# se_to_diff_v0001.net
KiCad netlist of a schematic drawn in EAGLE
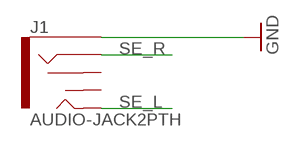
[diagram p0: schematic, sheet 1]
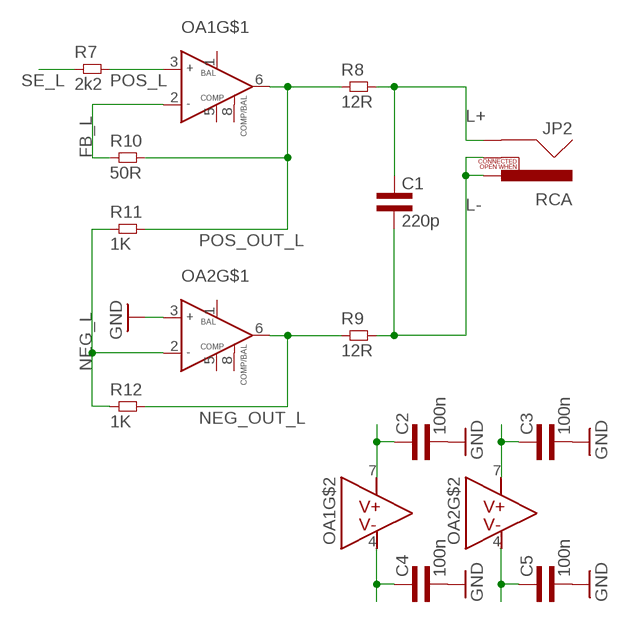
[diagram p1: schematic, sheet 2]
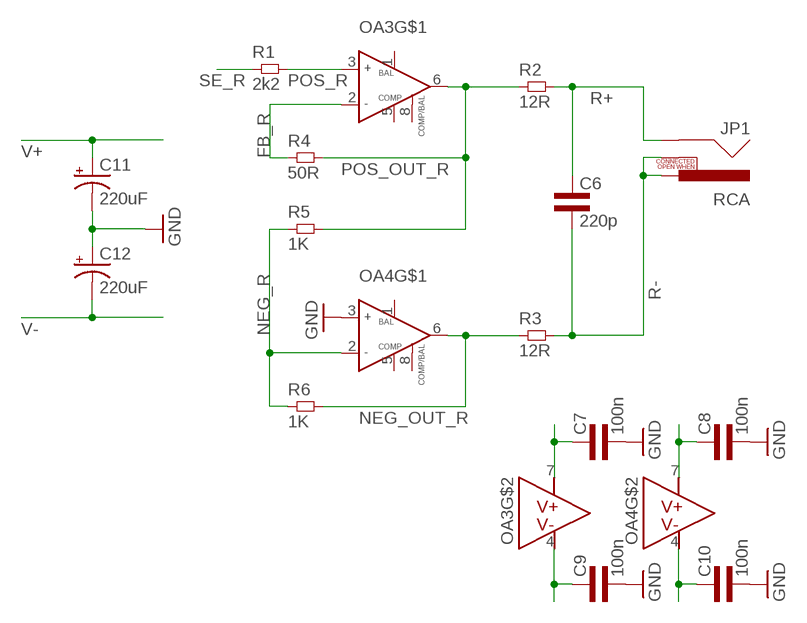
[diagram p2: schematic, sheet 3]

(export (version "E")
  (design (tool "Eeschema 10.0.6"))
  (components
    (comp (ref "C6")
      (value "220p")
      (footprint "eagle-import:0603L3")
      (libsource (lib "eagle-import") (part "CAP0603L3"))
    )
    (comp (ref "C7")
      (value "100n")
      (footprint "eagle-import:0603L3")
      (libsource (lib "eagle-import") (part "CAP0603L3"))
    )
    (comp (ref "C8")
      (value "100n")
      (footprint "eagle-import:0603L3")
      (libsource (lib "eagle-import") (part "CAP0603L3"))
    )
    (comp (ref "C9")
      (value "100n")
      (footprint "eagle-import:0603L3")
      (libsource (lib "eagle-import") (part "CAP0603L3"))
    )
    (comp (ref "C10")
      (value "100n")
      (footprint "eagle-import:0603L3")
      (libsource (lib "eagle-import") (part "CAP0603L3"))
    )
    (comp (ref "C11")
      (value "220uF")
      (footprint "eagle-import:CT7343")
      (libsource (lib "eagle-import") (part "CPOL-USCT7343"))
    )
    (comp (ref "C12")
      (value "220uF")
      (footprint "eagle-import:CT7343")
      (libsource (lib "eagle-import") (part "CPOL-USCT7343"))
    )
    (comp (ref "JP1")
      (value "RCA")
      (footprint "eagle-import:RCA")
      (libsource (lib "eagle-import") (part "RCA"))
    )
    (comp (ref "OA3")
      (value "NE5534DSOIC8")
      (footprint "eagle-import:SOIC-8")
      (libsource (lib "eagle-import") (part "NE5534SOIC8D"))
    )
    (comp (ref "OA4")
      (value "NE5534DSOIC8")
      (footprint "eagle-import:SOIC-8")
      (libsource (lib "eagle-import") (part "NE5534SOIC8D"))
    )
    (comp (ref "R1")
      (value "2k2")
      (footprint "eagle-import:0603L3")
      (libsource (lib "eagle-import") (part "RES0603L3"))
    )
    (comp (ref "R2")
      (value "12R")
      (footprint "eagle-import:0603L3")
      (libsource (lib "eagle-import") (part "RES0603L3"))
    )
    (comp (ref "R3")
      (value "12R")
      (footprint "eagle-import:0603L3")
      (libsource (lib "eagle-import") (part "RES0603L3"))
    )
    (comp (ref "R4")
      (value "50R")
      (footprint "eagle-import:0603L3")
      (libsource (lib "eagle-import") (part "RES0603L3"))
    )
    (comp (ref "R5")
      (value "1K")
      (footprint "eagle-import:0603L3")
      (libsource (lib "eagle-import") (part "RES0603L3"))
    )
    (comp (ref "R6")
      (value "1K")
      (footprint "eagle-import:0603L3")
      (libsource (lib "eagle-import") (part "RES0603L3"))
    )
    (comp (ref "C1")
      (value "220p")
      (footprint "eagle-import:0603L3")
      (libsource (lib "eagle-import") (part "CAP0603L3"))
    )
    (comp (ref "C2")
      (value "100n")
      (footprint "eagle-import:0603L3")
      (libsource (lib "eagle-import") (part "CAP0603L3"))
    )
    (comp (ref "C3")
      (value "100n")
      (footprint "eagle-import:0603L3")
      (libsource (lib "eagle-import") (part "CAP0603L3"))
    )
    (comp (ref "C4")
      (value "100n")
      (footprint "eagle-import:0603L3")
      (libsource (lib "eagle-import") (part "CAP0603L3"))
    )
    (comp (ref "C5")
      (value "100n")
      (footprint "eagle-import:0603L3")
      (libsource (lib "eagle-import") (part "CAP0603L3"))
    )
    (comp (ref "JP2")
      (value "RCA")
      (footprint "eagle-import:RCA")
      (libsource (lib "eagle-import") (part "RCA"))
    )
    (comp (ref "OA1")
      (value "NE5534DSOIC8")
      (footprint "eagle-import:SOIC-8")
      (libsource (lib "eagle-import") (part "NE5534SOIC8D"))
    )
    (comp (ref "OA2")
      (value "NE5534DSOIC8")
      (footprint "eagle-import:SOIC-8")
      (libsource (lib "eagle-import") (part "NE5534SOIC8D"))
    )
    (comp (ref "R7")
      (value "2k2")
      (footprint "eagle-import:0603L3")
      (libsource (lib "eagle-import") (part "RES0603L3"))
    )
    (comp (ref "R8")
      (value "12R")
      (footprint "eagle-import:0603L3")
      (libsource (lib "eagle-import") (part "RES0603L3"))
    )
    (comp (ref "R9")
      (value "12R")
      (footprint "eagle-import:0603L3")
      (libsource (lib "eagle-import") (part "RES0603L3"))
    )
    (comp (ref "R10")
      (value "50R")
      (footprint "eagle-import:0603L3")
      (libsource (lib "eagle-import") (part "RES0603L3"))
    )
    (comp (ref "R11")
      (value "1K")
      (footprint "eagle-import:0603L3")
      (libsource (lib "eagle-import") (part "RES0603L3"))
    )
    (comp (ref "R12")
      (value "1K")
      (footprint "eagle-import:0603L3")
      (libsource (lib "eagle-import") (part "RES0603L3"))
    )
    (comp (ref "J1")
      (value "AUDIO-JACK2PTH")
      (footprint "eagle-import:AUDIO-JACK")
      (libsource (lib "eagle-import") (part "AUDIO-JACK2PTH"))
    )
  )
  (nets
    (net (code "1") (name "FB_L") (class "Default")
      (node (ref "OA1") (pin "2") (pinfunction "IN-_2") (pintype "bidirectional"))
      (node (ref "R10") (pin "P$1") (pinfunction "1_P$1") (pintype "bidirectional"))
    )
    (net (code "2") (name "FB_R") (class "Default")
      (node (ref "OA3") (pin "2") (pinfunction "IN-_2") (pintype "bidirectional"))
      (node (ref "R4") (pin "P$1") (pinfunction "1_P$1") (pintype "bidirectional"))
    )
    (net (code "3") (name "GND") (class "Default")
      (node (ref "C10") (pin "P$2") (pinfunction "2_P$2") (pintype "bidirectional"))
      (node (ref "C11") (pin "-") (pinfunction "-_-") (pintype "passive"))
      (node (ref "C12") (pin "+") (pinfunction "+_+") (pintype "passive"))
      (node (ref "C2") (pin "P$2") (pinfunction "2_P$2") (pintype "bidirectional"))
      (node (ref "C3") (pin "P$2") (pinfunction "2_P$2") (pintype "bidirectional"))
      (node (ref "C4") (pin "P$2") (pinfunction "2_P$2") (pintype "bidirectional"))
      (node (ref "C5") (pin "P$2") (pinfunction "2_P$2") (pintype "bidirectional"))
      (node (ref "C7") (pin "P$2") (pinfunction "2_P$2") (pintype "bidirectional"))
      (node (ref "C8") (pin "P$2") (pinfunction "2_P$2") (pintype "bidirectional"))
      (node (ref "C9") (pin "P$2") (pinfunction "2_P$2") (pintype "bidirectional"))
      (node (ref "J1") (pin "SLEEVE") (pinfunction "SLEEVE_SLEEVE") (pintype "bidirectional"))
      (node (ref "OA2") (pin "3") (pinfunction "IN+_3") (pintype "bidirectional"))
      (node (ref "OA4") (pin "3") (pinfunction "IN+_3") (pintype "bidirectional"))
    )
    (net (code "4") (name "L+") (class "Default")
      (node (ref "C1") (pin "P$1") (pinfunction "1_P$1") (pintype "bidirectional"))
      (node (ref "JP2") (pin "SHELL") (pinfunction "SHELL_SHELL") (pintype "bidirectional"))
      (node (ref "R8") (pin "P$2") (pinfunction "2_P$2") (pintype "bidirectional"))
    )
    (net (code "5") (name "L-") (class "Default")
      (node (ref "C1") (pin "P$2") (pinfunction "2_P$2") (pintype "bidirectional"))
      (node (ref "JP2") (pin "PIN") (pinfunction "PIN_PIN") (pintype "bidirectional"))
      (node (ref "JP2") (pin "SWITCH") (pinfunction "SWITCH_SWITCH") (pintype "bidirectional"))
      (node (ref "R9") (pin "P$2") (pinfunction "2_P$2") (pintype "bidirectional"))
    )
    (net (code "6") (name "NEG_L") (class "Default")
      (node (ref "OA2") (pin "2") (pinfunction "IN-_2") (pintype "bidirectional"))
      (node (ref "R11") (pin "P$1") (pinfunction "1_P$1") (pintype "bidirectional"))
      (node (ref "R12") (pin "P$1") (pinfunction "1_P$1") (pintype "bidirectional"))
    )
    (net (code "7") (name "NEG_OUT_L") (class "Default")
      (node (ref "OA2") (pin "6") (pinfunction "OUT_6") (pintype "bidirectional"))
      (node (ref "R12") (pin "P$2") (pinfunction "2_P$2") (pintype "bidirectional"))
      (node (ref "R9") (pin "P$1") (pinfunction "1_P$1") (pintype "bidirectional"))
    )
    (net (code "8") (name "NEG_OUT_R") (class "Default")
      (node (ref "OA4") (pin "6") (pinfunction "OUT_6") (pintype "bidirectional"))
      (node (ref "R3") (pin "P$1") (pinfunction "1_P$1") (pintype "bidirectional"))
      (node (ref "R6") (pin "P$2") (pinfunction "2_P$2") (pintype "bidirectional"))
    )
    (net (code "9") (name "NEG_R") (class "Default")
      (node (ref "OA4") (pin "2") (pinfunction "IN-_2") (pintype "bidirectional"))
      (node (ref "R5") (pin "P$1") (pinfunction "1_P$1") (pintype "bidirectional"))
      (node (ref "R6") (pin "P$1") (pinfunction "1_P$1") (pintype "bidirectional"))
    )
    (net (code "10") (name "POS_L") (class "Default")
      (node (ref "OA1") (pin "3") (pinfunction "IN+_3") (pintype "bidirectional"))
      (node (ref "R7") (pin "P$2") (pinfunction "2_P$2") (pintype "bidirectional"))
    )
    (net (code "11") (name "POS_OUT_L") (class "Default")
      (node (ref "OA1") (pin "6") (pinfunction "OUT_6") (pintype "bidirectional"))
      (node (ref "R10") (pin "P$2") (pinfunction "2_P$2") (pintype "bidirectional"))
      (node (ref "R11") (pin "P$2") (pinfunction "2_P$2") (pintype "bidirectional"))
      (node (ref "R8") (pin "P$1") (pinfunction "1_P$1") (pintype "bidirectional"))
    )
    (net (code "12") (name "POS_OUT_R") (class "Default")
      (node (ref "OA3") (pin "6") (pinfunction "OUT_6") (pintype "bidirectional"))
      (node (ref "R2") (pin "P$1") (pinfunction "1_P$1") (pintype "bidirectional"))
      (node (ref "R4") (pin "P$2") (pinfunction "2_P$2") (pintype "bidirectional"))
      (node (ref "R5") (pin "P$2") (pinfunction "2_P$2") (pintype "bidirectional"))
    )
    (net (code "13") (name "POS_R") (class "Default")
      (node (ref "OA3") (pin "3") (pinfunction "IN+_3") (pintype "bidirectional"))
      (node (ref "R1") (pin "P$2") (pinfunction "2_P$2") (pintype "bidirectional"))
    )
    (net (code "14") (name "R+") (class "Default")
      (node (ref "C6") (pin "P$1") (pinfunction "1_P$1") (pintype "bidirectional"))
      (node (ref "JP1") (pin "SHELL") (pinfunction "SHELL_SHELL") (pintype "bidirectional"))
      (node (ref "R2") (pin "P$2") (pinfunction "2_P$2") (pintype "bidirectional"))
    )
    (net (code "15") (name "R-") (class "Default")
      (node (ref "C6") (pin "P$2") (pinfunction "2_P$2") (pintype "bidirectional"))
      (node (ref "JP1") (pin "PIN") (pinfunction "PIN_PIN") (pintype "bidirectional"))
      (node (ref "JP1") (pin "SWITCH") (pinfunction "SWITCH_SWITCH") (pintype "bidirectional"))
      (node (ref "R3") (pin "P$2") (pinfunction "2_P$2") (pintype "bidirectional"))
    )
    (net (code "16") (name "SE_L") (class "Default")
      (node (ref "J1") (pin "TIP") (pinfunction "TIP_TIP") (pintype "bidirectional"))
      (node (ref "R7") (pin "P$1") (pinfunction "1_P$1") (pintype "bidirectional"))
    )
    (net (code "17") (name "SE_R") (class "Default")
      (node (ref "J1") (pin "RING") (pinfunction "RING_RING") (pintype "bidirectional"))
      (node (ref "R1") (pin "P$1") (pinfunction "1_P$1") (pintype "bidirectional"))
    )
    (net (code "18") (name "V+") (class "Default")
      (node (ref "C11") (pin "+") (pinfunction "+_+") (pintype "passive"))
      (node (ref "C2") (pin "P$1") (pinfunction "1_P$1") (pintype "bidirectional"))
      (node (ref "C3") (pin "P$1") (pinfunction "1_P$1") (pintype "bidirectional"))
      (node (ref "C7") (pin "P$1") (pinfunction "1_P$1") (pintype "bidirectional"))
      (node (ref "C8") (pin "P$1") (pinfunction "1_P$1") (pintype "bidirectional"))
      (node (ref "OA1") (pin "7") (pinfunction "V+_7") (pintype "power_in"))
      (node (ref "OA2") (pin "7") (pinfunction "V+_7") (pintype "power_in"))
      (node (ref "OA3") (pin "7") (pinfunction "V+_7") (pintype "power_in"))
      (node (ref "OA4") (pin "7") (pinfunction "V+_7") (pintype "power_in"))
    )
    (net (code "19") (name "V-") (class "Default")
      (node (ref "C10") (pin "P$1") (pinfunction "1_P$1") (pintype "bidirectional"))
      (node (ref "C12") (pin "-") (pinfunction "-_-") (pintype "passive"))
      (node (ref "C4") (pin "P$1") (pinfunction "1_P$1") (pintype "bidirectional"))
      (node (ref "C5") (pin "P$1") (pinfunction "1_P$1") (pintype "bidirectional"))
      (node (ref "C9") (pin "P$1") (pinfunction "1_P$1") (pintype "bidirectional"))
      (node (ref "OA1") (pin "4") (pinfunction "V-_4") (pintype "power_in"))
      (node (ref "OA2") (pin "4") (pinfunction "V-_4") (pintype "power_in"))
      (node (ref "OA3") (pin "4") (pinfunction "V-_4") (pintype "power_in"))
      (node (ref "OA4") (pin "4") (pinfunction "V-_4") (pintype "power_in"))
    )
    (net (code "20") (name "unconnected-(J1-PadRSH)") (class "Default")
      (node (ref "J1") (pin "RSH") (pinfunction "RSH_RSH") (pintype "bidirectional"))
    )
    (net (code "21") (name "unconnected-(J1-PadTSH)") (class "Default")
      (node (ref "J1") (pin "TSH") (pinfunction "TSH_TSH") (pintype "bidirectional"))
    )
    (net (code "22") (name "unconnected-(OA1A-BAL-Pad1)") (class "Default")
      (node (ref "OA1") (pin "1") (pinfunction "BAL_1") (pintype "bidirectional"))
    )
    (net (code "23") (name "unconnected-(OA1A-COMP-Pad5)") (class "Default")
      (node (ref "OA1") (pin "5") (pinfunction "COMP_5") (pintype "bidirectional"))
    )
    (net (code "24") (name "unconnected-(OA1A-COMP{slash}BAL-Pad8)") (class "Default")
      (node (ref "OA1") (pin "8") (pinfunction "COMP/BAL_8") (pintype "bidirectional"))
    )
    (net (code "25") (name "unconnected-(OA2A-BAL-Pad1)") (class "Default")
      (node (ref "OA2") (pin "1") (pinfunction "BAL_1") (pintype "bidirectional"))
    )
    (net (code "26") (name "unconnected-(OA2A-COMP-Pad5)") (class "Default")
      (node (ref "OA2") (pin "5") (pinfunction "COMP_5") (pintype "bidirectional"))
    )
    (net (code "27") (name "unconnected-(OA2A-COMP{slash}BAL-Pad8)") (class "Default")
      (node (ref "OA2") (pin "8") (pinfunction "COMP/BAL_8") (pintype "bidirectional"))
    )
    (net (code "28") (name "unconnected-(OA3A-BAL-Pad1)") (class "Default")
      (node (ref "OA3") (pin "1") (pinfunction "BAL_1") (pintype "bidirectional"))
    )
    (net (code "29") (name "unconnected-(OA3A-COMP-Pad5)") (class "Default")
      (node (ref "OA3") (pin "5") (pinfunction "COMP_5") (pintype "bidirectional"))
    )
    (net (code "30") (name "unconnected-(OA3A-COMP{slash}BAL-Pad8)") (class "Default")
      (node (ref "OA3") (pin "8") (pinfunction "COMP/BAL_8") (pintype "bidirectional"))
    )
    (net (code "31") (name "unconnected-(OA4A-BAL-Pad1)") (class "Default")
      (node (ref "OA4") (pin "1") (pinfunction "BAL_1") (pintype "bidirectional"))
    )
    (net (code "32") (name "unconnected-(OA4A-COMP-Pad5)") (class "Default")
      (node (ref "OA4") (pin "5") (pinfunction "COMP_5") (pintype "bidirectional"))
    )
    (net (code "33") (name "unconnected-(OA4A-COMP{slash}BAL-Pad8)") (class "Default")
      (node (ref "OA4") (pin "8") (pinfunction "COMP/BAL_8") (pintype "bidirectional"))
    )
  )
)
